# Power_supply.net
KiCad netlist of a schematic drawn in Altium Designer
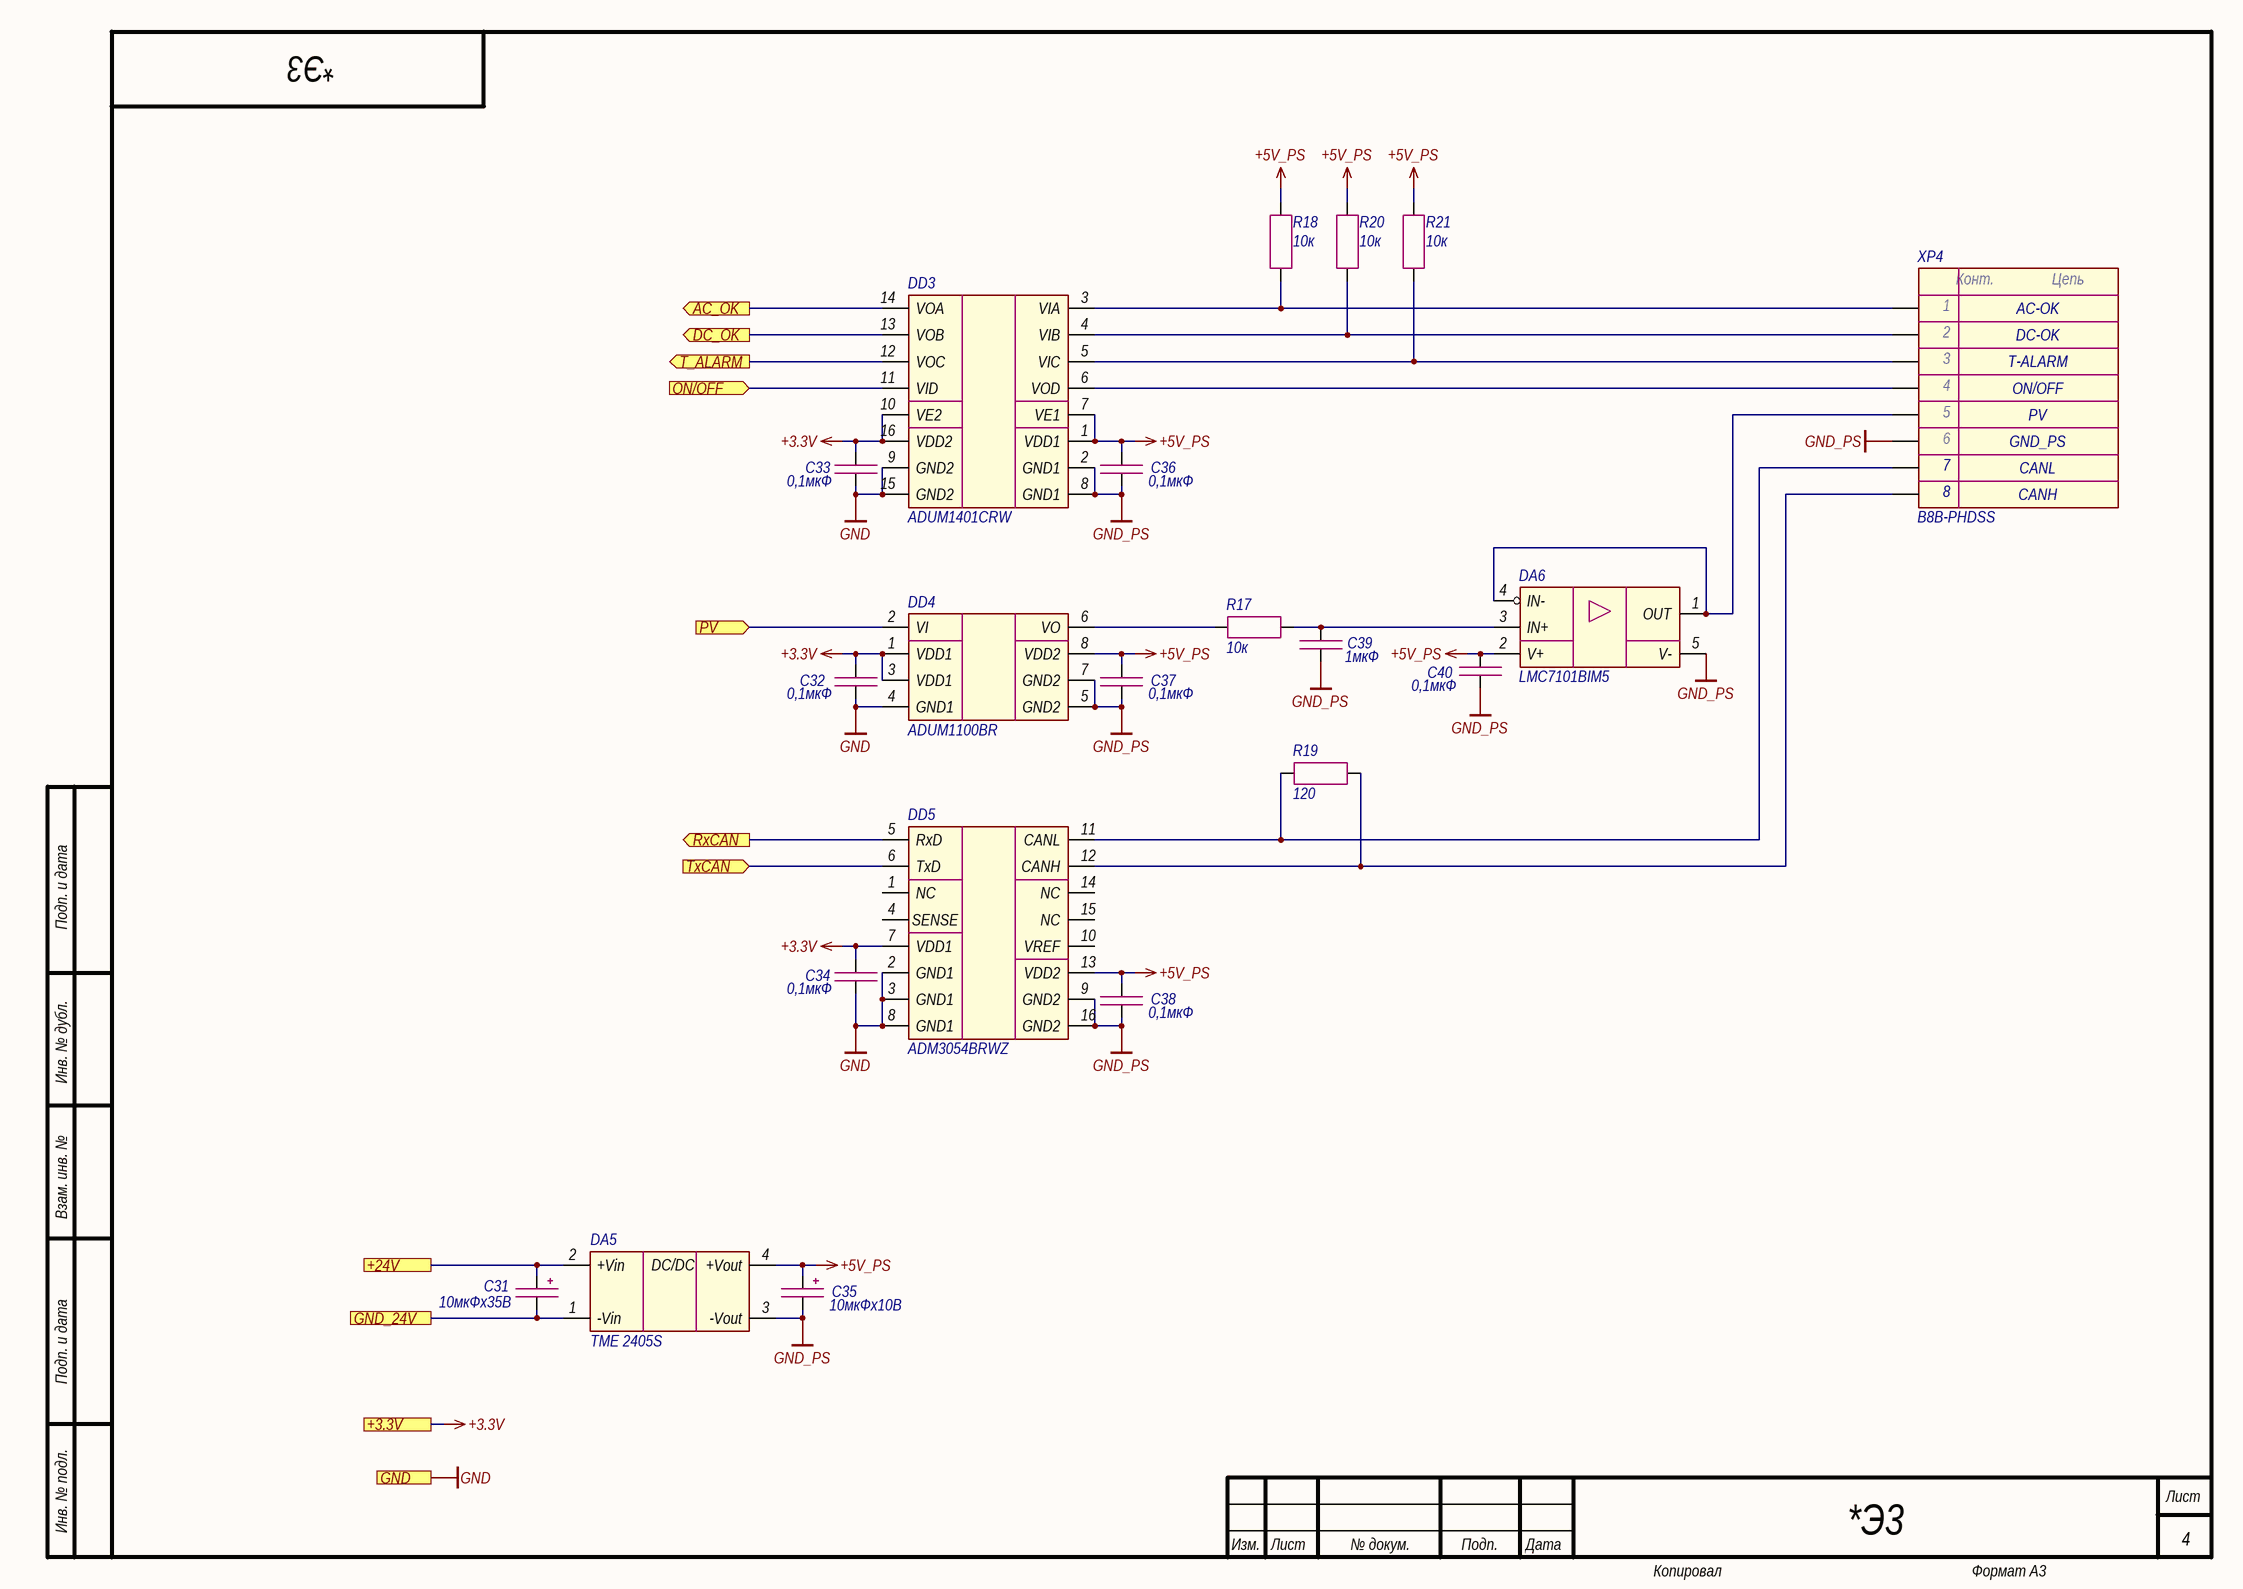
[diagram p0: Power_supply.SchDoc]

(export (version "E")
  (design (tool "Eeschema 10.0.6"))
  (components
    (comp (ref "C31")
      (value "10мкФх35B")
      (footprint "Pcb_library:CAP_C")
      (libsource (lib "Schem_library") (part "Capacitor_Polar"))
    )
    (comp (ref "C32")
      (value "0,1мкФ")
      (footprint "Pcb_library:CAP_0603")
      (fields (field (name "MANUFACTURER") "Murata"))
      (libsource (lib "Schem_library") (part "Capacitor"))
    )
    (comp (ref "C33")
      (value "0,1мкФ")
      (footprint "Pcb_library:CAP_0603")
      (fields (field (name "MANUFACTURER") "Murata"))
      (libsource (lib "Schem_library") (part "Capacitor"))
    )
    (comp (ref "C34")
      (value "0,1мкФ")
      (footprint "Pcb_library:CAP_0603")
      (fields (field (name "MANUFACTURER") "Murata"))
      (libsource (lib "Schem_library") (part "Capacitor"))
    )
    (comp (ref "C35")
      (value "10мкФх10B")
      (footprint "Pcb_library:CAP_A")
      (libsource (lib "Schem_library") (part "Capacitor_Polar"))
    )
    (comp (ref "C36")
      (value "0,1мкФ")
      (footprint "Pcb_library:CAP_0603")
      (fields (field (name "MANUFACTURER") "Murata"))
      (libsource (lib "Schem_library") (part "Capacitor"))
    )
    (comp (ref "C37")
      (value "0,1мкФ")
      (footprint "Pcb_library:CAP_0603")
      (fields (field (name "MANUFACTURER") "Murata"))
      (libsource (lib "Schem_library") (part "Capacitor"))
    )
    (comp (ref "C38")
      (value "0,1мкФ")
      (footprint "Pcb_library:CAP_0603")
      (fields (field (name "MANUFACTURER") "Murata"))
      (libsource (lib "Schem_library") (part "Capacitor"))
    )
    (comp (ref "C39")
      (value "1мкФ")
      (footprint "Pcb_library:CAP_0603")
      (fields (field (name "MANUFACTURER") "Murata"))
      (libsource (lib "Schem_library") (part "Capacitor"))
    )
    (comp (ref "C40")
      (value "0,1мкФ")
      (footprint "Pcb_library:CAP_0603")
      (fields (field (name "MANUFACTURER") "Murata"))
      (libsource (lib "Schem_library") (part "Capacitor"))
    )
    (comp (ref "DA5")
      (value "TME 2405S")
      (footprint "Pcb_library:TME (SIP-4)")
      (fields (field (name "MANUFACTURER") "Traco Power"))
      (libsource (lib "Schem_library") (part "TME"))
    )
    (comp (ref "DA6")
      (value "LMC7101BIM5")
      (footprint "Pcb_library:SOT-23-5")
      (fields (field (name "MANUFACTURER") "Texas Instruments"))
      (libsource (lib "Schem_library") (part "LMC7101"))
    )
    (comp (ref "DD3")
      (value "ADUM1401CRW")
      (footprint "Pcb_library:SOIC-16W")
      (fields (field (name "MANUFACTURER") "Analog Devices"))
      (libsource (lib "Schem_library") (part "ADUM1401"))
    )
    (comp (ref "DD4")
      (value "ADUM1100BR")
      (footprint "Pcb_library:SOIC-8")
      (fields (field (name "MANUFACTURER") "Analog Devices"))
      (libsource (lib "Schem_library") (part "ADUM1100"))
    )
    (comp (ref "DD5")
      (value "ADM3054BRWZ")
      (footprint "Pcb_library:SOIC-16W")
      (fields (field (name "MANUFACTURER") "Analog Devices"))
      (libsource (lib "Schem_library") (part "ADM3054BRWZ"))
    )
    (comp (ref "R17")
      (value "10к")
      (footprint "Pcb_library:RES_0603")
      (fields (field (name "MANUFACTURER") "Yageo"))
      (libsource (lib "Schem_library") (part "Resistor"))
    )
    (comp (ref "R18")
      (value "10к")
      (footprint "Pcb_library:RES_0603")
      (fields (field (name "MANUFACTURER") "Yageo"))
      (libsource (lib "Schem_library") (part "Resistor"))
    )
    (comp (ref "R19")
      (value "120")
      (footprint "Pcb_library:RES_0805")
      (fields (field (name "MANUFACTURER") "Yageo"))
      (libsource (lib "Schem_library") (part "Resistor"))
    )
    (comp (ref "R20")
      (value "10к")
      (footprint "Pcb_library:RES_0603")
      (fields (field (name "MANUFACTURER") "Yageo"))
      (libsource (lib "Schem_library") (part "Resistor"))
    )
    (comp (ref "R21")
      (value "10к")
      (footprint "Pcb_library:RES_0603")
      (fields (field (name "MANUFACTURER") "Yageo"))
      (libsource (lib "Schem_library") (part "Resistor"))
    )
    (comp (ref "XP4")
      (value "B8B-PHDSS")
      (footprint "Pcb_library:B8B-PHDSS")
      (fields (field (name "MANUFACTURER") "JST"))
      (libsource (lib "Schem_library") (part "Connector-8"))
    )
  )
  (nets
    (net (code "1") (name "+3.3V") (class "Default")
      (node (ref "C32") (pin "1") (pinfunction "1_1") (pintype "passive"))
      (node (ref "C33") (pin "1") (pinfunction "1_1") (pintype "passive"))
      (node (ref "C34") (pin "1") (pinfunction "1_1") (pintype "passive"))
      (node (ref "DD3") (pin "10") (pinfunction "VE2_10") (pintype "passive"))
      (node (ref "DD3") (pin "16") (pinfunction "VDD2_16") (pintype "passive"))
      (node (ref "DD4") (pin "1") (pinfunction "VDD1_1") (pintype "passive"))
      (node (ref "DD4") (pin "3") (pinfunction "VDD1_3") (pintype "passive"))
      (node (ref "DD5") (pin "7") (pinfunction "VDD1_7") (pintype "passive"))
    )
    (net (code "2") (name "+5V_PS") (class "Default")
      (node (ref "C35") (pin "1") (pinfunction "1_1") (pintype "passive"))
      (node (ref "C36") (pin "1") (pinfunction "1_1") (pintype "passive"))
      (node (ref "C37") (pin "1") (pinfunction "1_1") (pintype "passive"))
      (node (ref "C38") (pin "1") (pinfunction "1_1") (pintype "passive"))
      (node (ref "C40") (pin "1") (pinfunction "1_1") (pintype "passive"))
      (node (ref "DA5") (pin "4") (pinfunction "+Vout_4") (pintype "passive"))
      (node (ref "DA6") (pin "2") (pinfunction "V+_2") (pintype "passive"))
      (node (ref "DD3") (pin "1") (pinfunction "VDD1_1") (pintype "passive"))
      (node (ref "DD3") (pin "7") (pinfunction "VE1_7") (pintype "passive"))
      (node (ref "DD4") (pin "8") (pinfunction "VDD2_8") (pintype "passive"))
      (node (ref "DD5") (pin "13") (pinfunction "VDD2_13") (pintype "passive"))
      (node (ref "R18") (pin "1") (pinfunction "1_1") (pintype "passive"))
      (node (ref "R20") (pin "1") (pinfunction "1_1") (pintype "passive"))
      (node (ref "R21") (pin "1") (pinfunction "1_1") (pintype "passive"))
    )
    (net (code "3") (name "/+24V") (class "Default")
      (node (ref "C31") (pin "1") (pinfunction "1_1") (pintype "passive"))
      (node (ref "DA5") (pin "2") (pinfunction "+Vin_2") (pintype "passive"))
    )
    (net (code "4") (name "/AC_OK") (class "Default")
      (node (ref "DD3") (pin "14") (pinfunction "VOA_14") (pintype "passive"))
    )
    (net (code "5") (name "/DC_OK") (class "Default")
      (node (ref "DD3") (pin "13") (pinfunction "VOB_13") (pintype "passive"))
    )
    (net (code "6") (name "/GND_24V") (class "Default")
      (node (ref "C31") (pin "2") (pinfunction "2_2") (pintype "passive"))
      (node (ref "DA5") (pin "1") (pinfunction "-Vin_1") (pintype "passive"))
    )
    (net (code "7") (name "/ON{slash}OFF") (class "Default")
      (node (ref "DD3") (pin "11") (pinfunction "VID_11") (pintype "passive"))
    )
    (net (code "8") (name "/PV") (class "Default")
      (node (ref "DD4") (pin "2") (pinfunction "VI_2") (pintype "passive"))
    )
    (net (code "9") (name "/RxCAN") (class "Default")
      (node (ref "DD5") (pin "5") (pinfunction "RxD_5") (pintype "passive"))
    )
    (net (code "10") (name "/T_ALARM") (class "Default")
      (node (ref "DD3") (pin "12") (pinfunction "VOC_12") (pintype "passive"))
    )
    (net (code "11") (name "/TxCAN") (class "Default")
      (node (ref "DD5") (pin "6") (pinfunction "TxD_6") (pintype "passive"))
    )
    (net (code "12") (name "GND") (class "Default")
      (node (ref "C32") (pin "2") (pinfunction "2_2") (pintype "passive"))
      (node (ref "C33") (pin "2") (pinfunction "2_2") (pintype "passive"))
      (node (ref "C34") (pin "2") (pinfunction "2_2") (pintype "passive"))
      (node (ref "DD3") (pin "15") (pinfunction "GND2_15") (pintype "passive"))
      (node (ref "DD3") (pin "9") (pinfunction "GND2_9") (pintype "passive"))
      (node (ref "DD4") (pin "4") (pinfunction "GND1_4") (pintype "passive"))
      (node (ref "DD5") (pin "2") (pinfunction "GND1_2") (pintype "passive"))
      (node (ref "DD5") (pin "3") (pinfunction "GND1_3") (pintype "passive"))
      (node (ref "DD5") (pin "8") (pinfunction "GND1_8") (pintype "passive"))
    )
    (net (code "13") (name "GND_PS") (class "Default")
      (node (ref "C35") (pin "2") (pinfunction "2_2") (pintype "passive"))
      (node (ref "C36") (pin "2") (pinfunction "2_2") (pintype "passive"))
      (node (ref "C37") (pin "2") (pinfunction "2_2") (pintype "passive"))
      (node (ref "C38") (pin "2") (pinfunction "2_2") (pintype "passive"))
      (node (ref "C39") (pin "2") (pinfunction "2_2") (pintype "passive"))
      (node (ref "C40") (pin "2") (pinfunction "2_2") (pintype "passive"))
      (node (ref "DA5") (pin "3") (pinfunction "-Vout_3") (pintype "passive"))
      (node (ref "DA6") (pin "5") (pinfunction "V-_5") (pintype "passive"))
      (node (ref "DD3") (pin "2") (pinfunction "GND1_2") (pintype "passive"))
      (node (ref "DD3") (pin "8") (pinfunction "GND1_8") (pintype "passive"))
      (node (ref "DD4") (pin "5") (pinfunction "GND2_5") (pintype "passive"))
      (node (ref "DD4") (pin "7") (pinfunction "GND2_7") (pintype "passive"))
      (node (ref "DD5") (pin "16") (pinfunction "GND2_16") (pintype "passive"))
      (node (ref "DD5") (pin "9") (pinfunction "GND2_9") (pintype "passive"))
      (node (ref "XP4") (pin "6") (pintype "passive"))
    )
    (net (code "14") (name "Net-(DA6-IN+)") (class "Default")
      (node (ref "C39") (pin "1") (pinfunction "1_1") (pintype "passive"))
      (node (ref "DA6") (pin "3") (pinfunction "IN+_3") (pintype "passive"))
      (node (ref "R17") (pin "2") (pinfunction "2_2") (pintype "passive"))
    )
    (net (code "15") (name "Net-(DA6-IN-)") (class "Default")
      (node (ref "DA6") (pin "1") (pinfunction "OUT_1") (pintype "passive"))
      (node (ref "DA6") (pin "4") (pinfunction "IN-_4") (pintype "passive"))
      (node (ref "XP4") (pin "5") (pintype "passive"))
    )
    (net (code "16") (name "Net-(DD3-VIA)") (class "Default")
      (node (ref "DD3") (pin "3") (pinfunction "VIA_3") (pintype "passive"))
      (node (ref "R18") (pin "2") (pinfunction "2_2") (pintype "passive"))
      (node (ref "XP4") (pin "1") (pintype "passive"))
    )
    (net (code "17") (name "Net-(DD3-VIB)") (class "Default")
      (node (ref "DD3") (pin "4") (pinfunction "VIB_4") (pintype "passive"))
      (node (ref "R20") (pin "2") (pinfunction "2_2") (pintype "passive"))
      (node (ref "XP4") (pin "2") (pintype "passive"))
    )
    (net (code "18") (name "Net-(DD3-VIC)") (class "Default")
      (node (ref "DD3") (pin "5") (pinfunction "VIC_5") (pintype "passive"))
      (node (ref "R21") (pin "2") (pinfunction "2_2") (pintype "passive"))
      (node (ref "XP4") (pin "3") (pintype "passive"))
    )
    (net (code "19") (name "Net-(DD3-VOD)") (class "Default")
      (node (ref "DD3") (pin "6") (pinfunction "VOD_6") (pintype "passive"))
      (node (ref "XP4") (pin "4") (pintype "passive"))
    )
    (net (code "20") (name "Net-(DD4-VO)") (class "Default")
      (node (ref "DD4") (pin "6") (pinfunction "VO_6") (pintype "passive"))
      (node (ref "R17") (pin "1") (pinfunction "1_1") (pintype "passive"))
    )
    (net (code "21") (name "Net-(DD5-CANH)") (class "Default")
      (node (ref "DD5") (pin "12") (pinfunction "CANH_12") (pintype "passive"))
      (node (ref "R19") (pin "2") (pinfunction "2_2") (pintype "passive"))
      (node (ref "XP4") (pin "8") (pintype "passive"))
    )
    (net (code "22") (name "Net-(DD5-CANL)") (class "Default")
      (node (ref "DD5") (pin "11") (pinfunction "CANL_11") (pintype "passive"))
      (node (ref "R19") (pin "1") (pinfunction "1_1") (pintype "passive"))
      (node (ref "XP4") (pin "7") (pintype "passive"))
    )
    (net (code "23") (name "unconnected-(DD5-NC-Pad1)") (class "Default")
      (node (ref "DD5") (pin "1") (pinfunction "NC_1") (pintype "passive"))
    )
    (net (code "24") (name "unconnected-(DD5-NC-Pad14)") (class "Default")
      (node (ref "DD5") (pin "14") (pinfunction "NC_14") (pintype "passive"))
    )
    (net (code "25") (name "unconnected-(DD5-NC-Pad15)") (class "Default")
      (node (ref "DD5") (pin "15") (pinfunction "NC_15") (pintype "passive"))
    )
    (net (code "26") (name "unconnected-(DD5-SENSE-Pad4)") (class "Default")
      (node (ref "DD5") (pin "4") (pinfunction "SENSE_4") (pintype "passive"))
    )
    (net (code "27") (name "unconnected-(DD5-VREF-Pad10)") (class "Default")
      (node (ref "DD5") (pin "10") (pinfunction "VREF_10") (pintype "passive"))
    )
  )
)
